# IOB-LED-Monitor.net
KiCad netlist of a schematic drawn in EAGLE
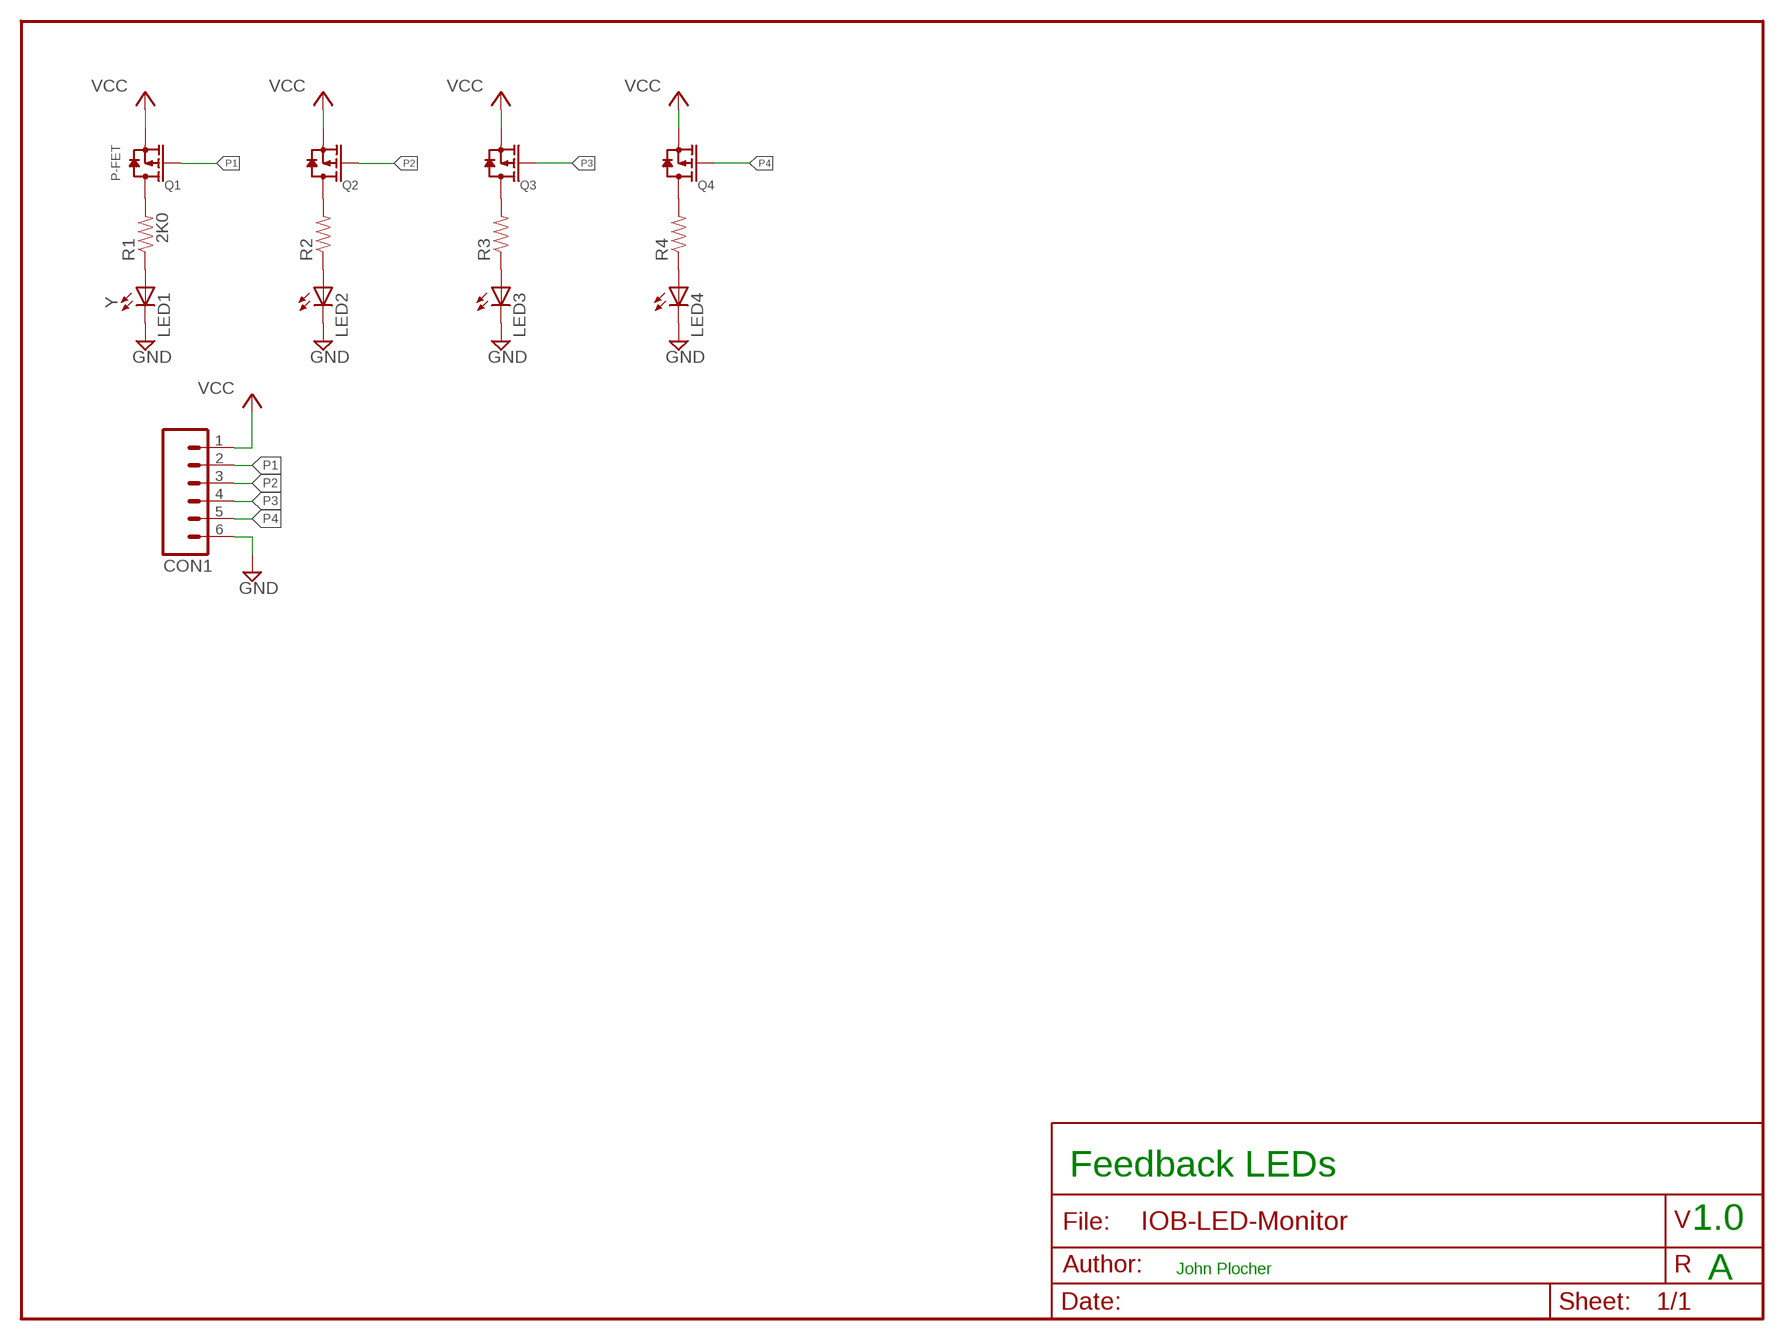
[diagram p0: schematic, sheet 1]

(export (version "E")
  (design (tool "Eeschema 10.0.6"))
  (components
    (comp (ref "CON1")
      (value "CONNECTOR-M06LOCK")
      (footprint "eagle-import:1X06_LOCK")
      (libsource (lib "eagle-import") (part "CONNECTOR-M06LOCK"))
    )
    (comp (ref "LED1")
      (value "Y")
      (footprint "eagle-import:0603-LED")
      (libsource (lib "eagle-import") (part "LED0603-LED"))
    )
    (comp (ref "LED2")
      (value "Y")
      (footprint "eagle-import:0603-LED")
      (libsource (lib "eagle-import") (part "LED0603-LED"))
    )
    (comp (ref "LED3")
      (value "Y")
      (footprint "eagle-import:0603-LED")
      (libsource (lib "eagle-import") (part "LED0603-LED"))
    )
    (comp (ref "LED4")
      (value "Y")
      (footprint "eagle-import:0603-LED")
      (libsource (lib "eagle-import") (part "LED0603-LED"))
    )
    (comp (ref "Q1")
      (value "P-FET")
      (footprint "eagle-import:SOT23")
      (libsource (lib "eagle-import") (part "MOSFET-P-044021001"))
    )
    (comp (ref "Q2")
      (value "P-FET")
      (footprint "eagle-import:SOT23")
      (libsource (lib "eagle-import") (part "MOSFET-P-044021001"))
    )
    (comp (ref "Q3")
      (value "P-FET")
      (footprint "eagle-import:SOT23")
      (libsource (lib "eagle-import") (part "MOSFET-P-044021001"))
    )
    (comp (ref "Q4")
      (value "P-FET")
      (footprint "eagle-import:SOT23")
      (libsource (lib "eagle-import") (part "MOSFET-P-044021001"))
    )
    (comp (ref "R1")
      (value "2K0")
      (footprint "eagle-import:0805-RES")
      (libsource (lib "eagle-import") (part "R0805-RES"))
    )
    (comp (ref "R2")
      (value "2K0")
      (footprint "eagle-import:0805-RES")
      (libsource (lib "eagle-import") (part "R0805-RES"))
    )
    (comp (ref "R3")
      (value "2K0")
      (footprint "eagle-import:0805-RES")
      (libsource (lib "eagle-import") (part "R0805-RES"))
    )
    (comp (ref "R4")
      (value "2K0")
      (footprint "eagle-import:0805-RES")
      (libsource (lib "eagle-import") (part "R0805-RES"))
    )
  )
  (nets
    (net (code "1") (name "GND") (class "Default")
      (node (ref "CON1") (pin "6") (pinfunction "6_6") (pintype "passive"))
      (node (ref "LED1") (pin "C") (pinfunction "C_C") (pintype "passive"))
      (node (ref "LED2") (pin "C") (pinfunction "C_C") (pintype "passive"))
      (node (ref "LED3") (pin "C") (pinfunction "C_C") (pintype "passive"))
      (node (ref "LED4") (pin "C") (pinfunction "C_C") (pintype "passive"))
    )
    (net (code "2") (name "Net-(LED1-PadA)") (class "Default")
      (node (ref "LED1") (pin "A") (pinfunction "A_A") (pintype "passive"))
      (node (ref "R1") (pin "1") (pinfunction "1_1") (pintype "passive"))
    )
    (net (code "3") (name "Net-(LED2-PadA)") (class "Default")
      (node (ref "LED2") (pin "A") (pinfunction "A_A") (pintype "passive"))
      (node (ref "R2") (pin "1") (pinfunction "1_1") (pintype "passive"))
    )
    (net (code "4") (name "Net-(LED3-PadA)") (class "Default")
      (node (ref "LED3") (pin "A") (pinfunction "A_A") (pintype "passive"))
      (node (ref "R3") (pin "1") (pinfunction "1_1") (pintype "passive"))
    )
    (net (code "5") (name "Net-(LED4-PadA)") (class "Default")
      (node (ref "LED4") (pin "A") (pinfunction "A_A") (pintype "passive"))
      (node (ref "R4") (pin "1") (pinfunction "1_1") (pintype "passive"))
    )
    (net (code "6") (name "Net-(Q1-D)") (class "Default")
      (node (ref "Q1") (pin "3") (pinfunction "D_3") (pintype "passive"))
      (node (ref "R1") (pin "2") (pinfunction "2_2") (pintype "passive"))
    )
    (net (code "7") (name "Net-(Q2-D)") (class "Default")
      (node (ref "Q2") (pin "3") (pinfunction "D_3") (pintype "passive"))
      (node (ref "R2") (pin "2") (pinfunction "2_2") (pintype "passive"))
    )
    (net (code "8") (name "Net-(Q3-D)") (class "Default")
      (node (ref "Q3") (pin "3") (pinfunction "D_3") (pintype "passive"))
      (node (ref "R3") (pin "2") (pinfunction "2_2") (pintype "passive"))
    )
    (net (code "9") (name "Net-(Q4-D)") (class "Default")
      (node (ref "Q4") (pin "3") (pinfunction "D_3") (pintype "passive"))
      (node (ref "R4") (pin "2") (pinfunction "2_2") (pintype "passive"))
    )
    (net (code "10") (name "P1") (class "Default")
      (node (ref "CON1") (pin "2") (pinfunction "2_2") (pintype "passive"))
      (node (ref "Q1") (pin "1") (pinfunction "G_1") (pintype "passive"))
    )
    (net (code "11") (name "P2") (class "Default")
      (node (ref "CON1") (pin "3") (pinfunction "3_3") (pintype "passive"))
      (node (ref "Q2") (pin "1") (pinfunction "G_1") (pintype "passive"))
    )
    (net (code "12") (name "P3") (class "Default")
      (node (ref "CON1") (pin "4") (pinfunction "4_4") (pintype "passive"))
      (node (ref "Q3") (pin "1") (pinfunction "G_1") (pintype "passive"))
    )
    (net (code "13") (name "P4") (class "Default")
      (node (ref "CON1") (pin "5") (pinfunction "5_5") (pintype "passive"))
      (node (ref "Q4") (pin "1") (pinfunction "G_1") (pintype "passive"))
    )
    (net (code "14") (name "VCC") (class "Default")
      (node (ref "CON1") (pin "1") (pinfunction "1_1") (pintype "passive"))
      (node (ref "Q1") (pin "2") (pinfunction "S_2") (pintype "passive"))
      (node (ref "Q2") (pin "2") (pinfunction "S_2") (pintype "passive"))
      (node (ref "Q3") (pin "2") (pinfunction "S_2") (pintype "passive"))
      (node (ref "Q4") (pin "2") (pinfunction "S_2") (pintype "passive"))
    )
  )
)
